# m365_esp32.net
KiCad netlist of a schematic drawn in EAGLE
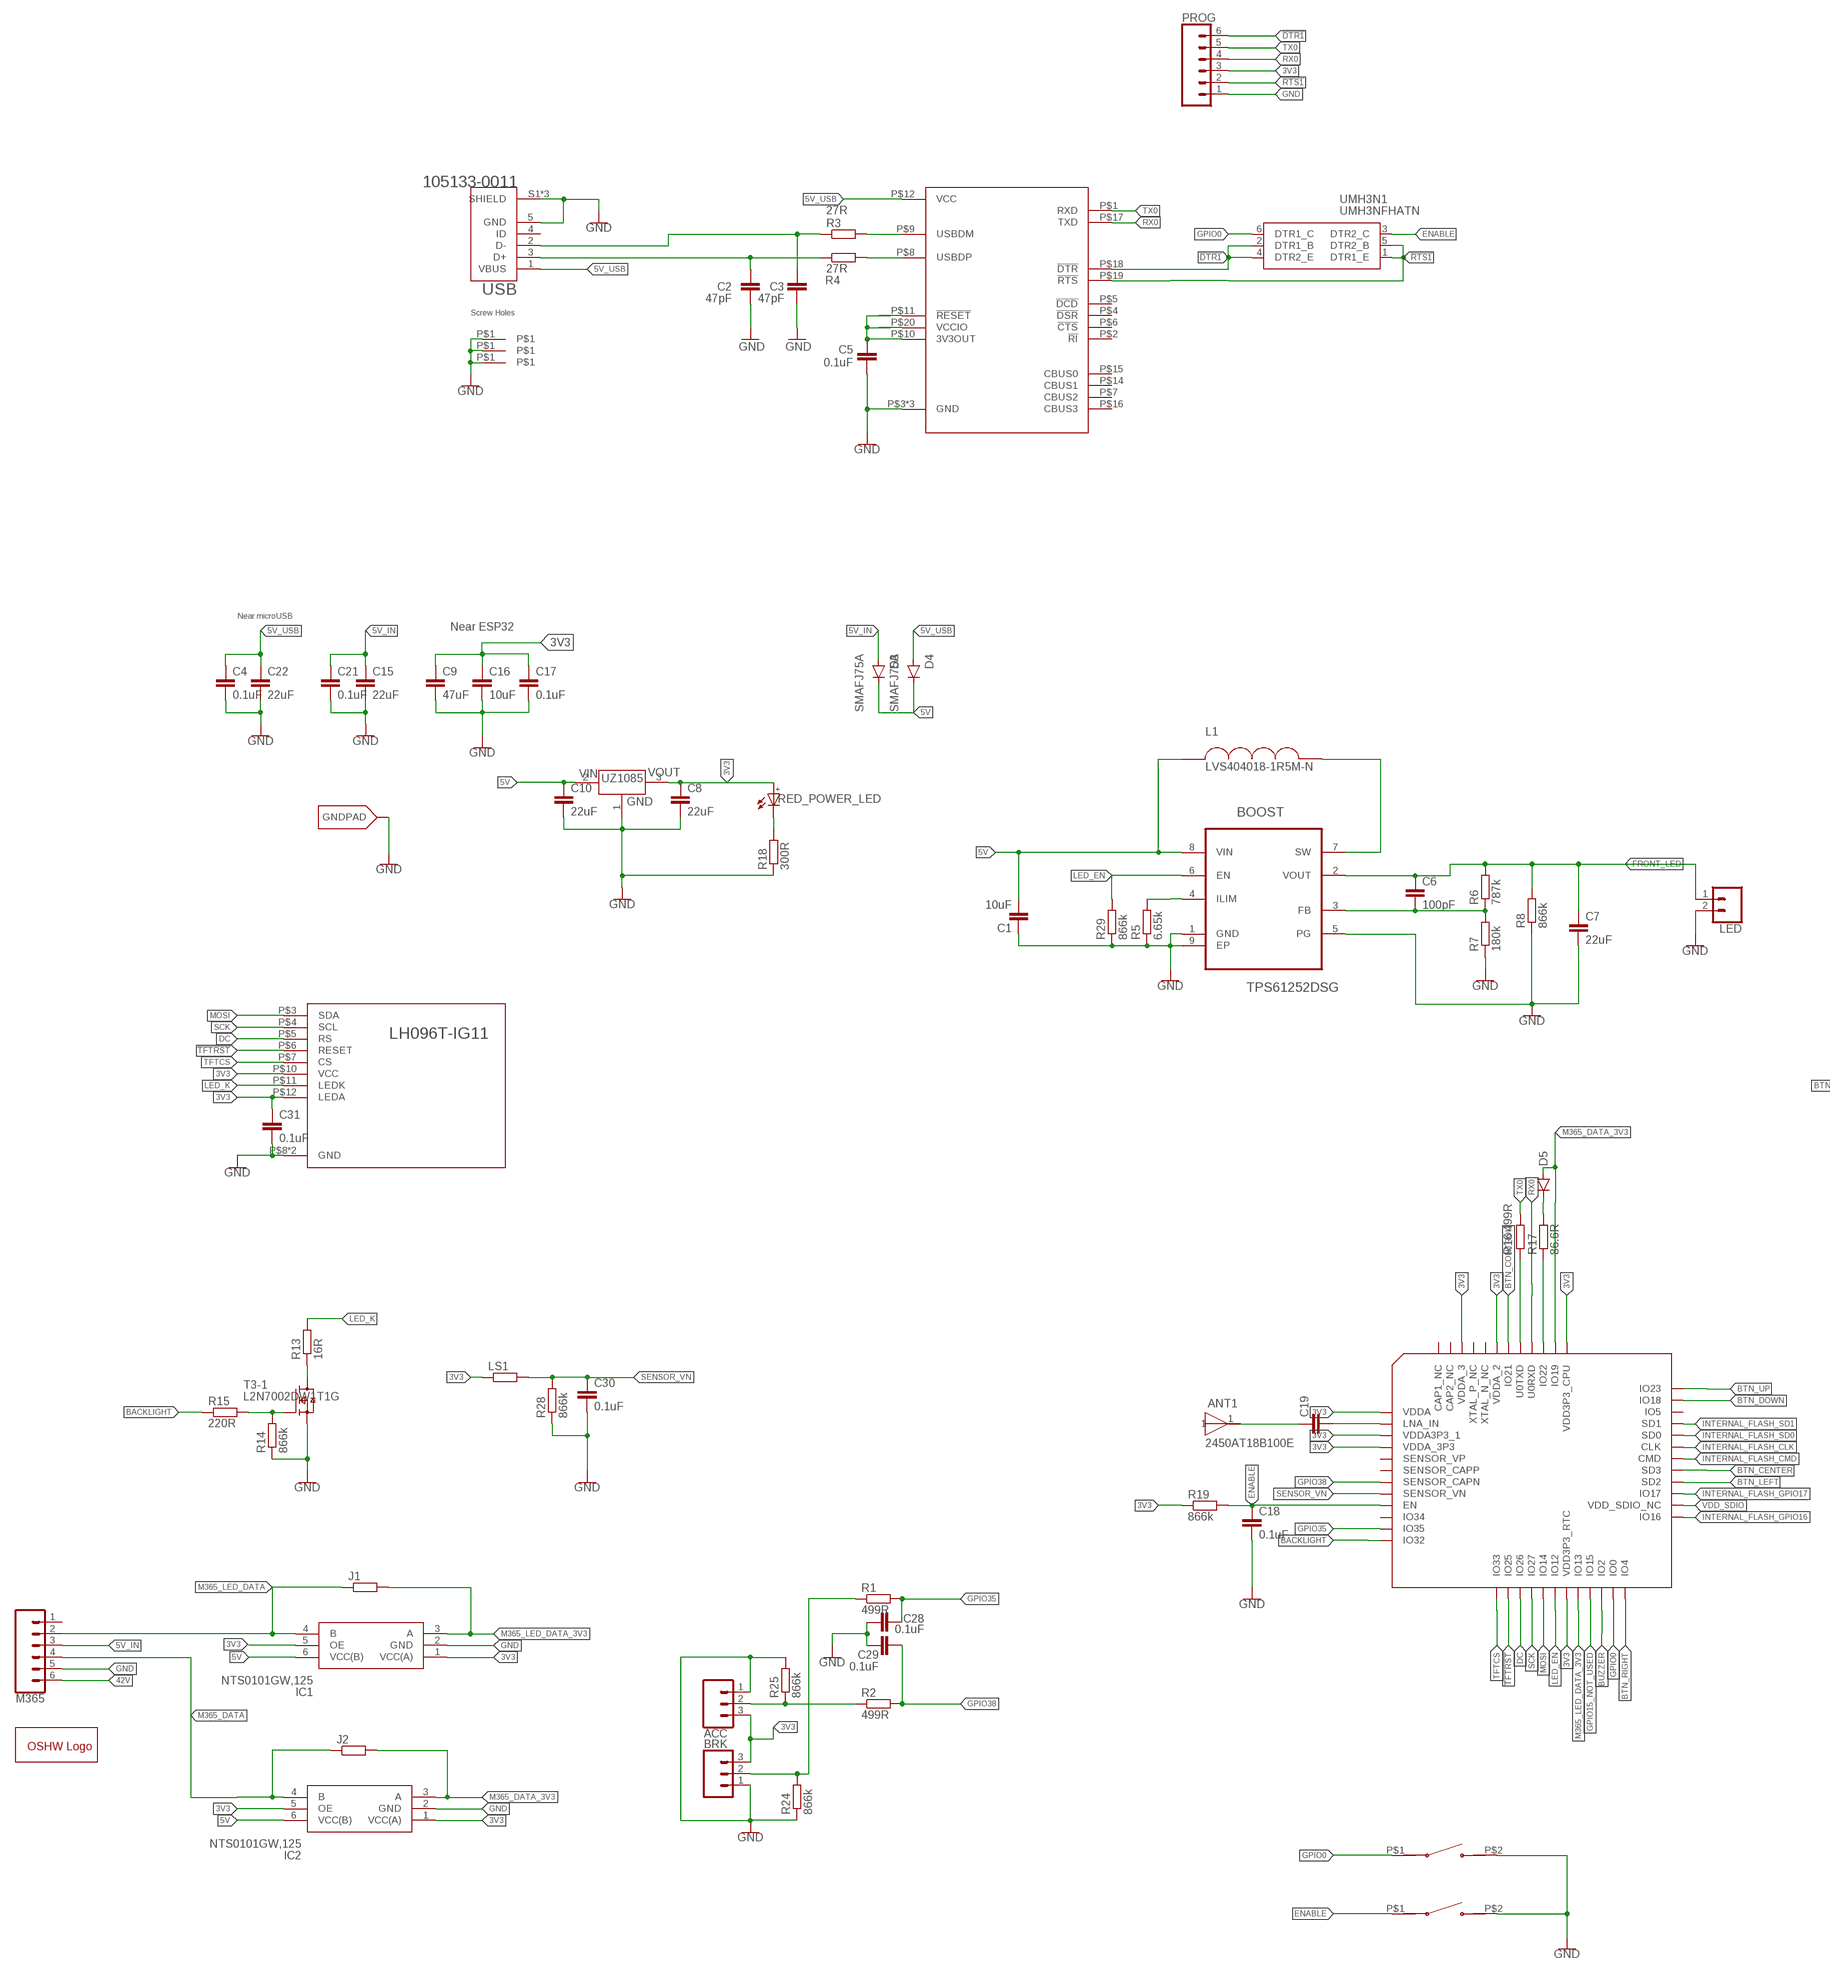
[diagram p0: schematic, sheet 1, part 1 of 2]
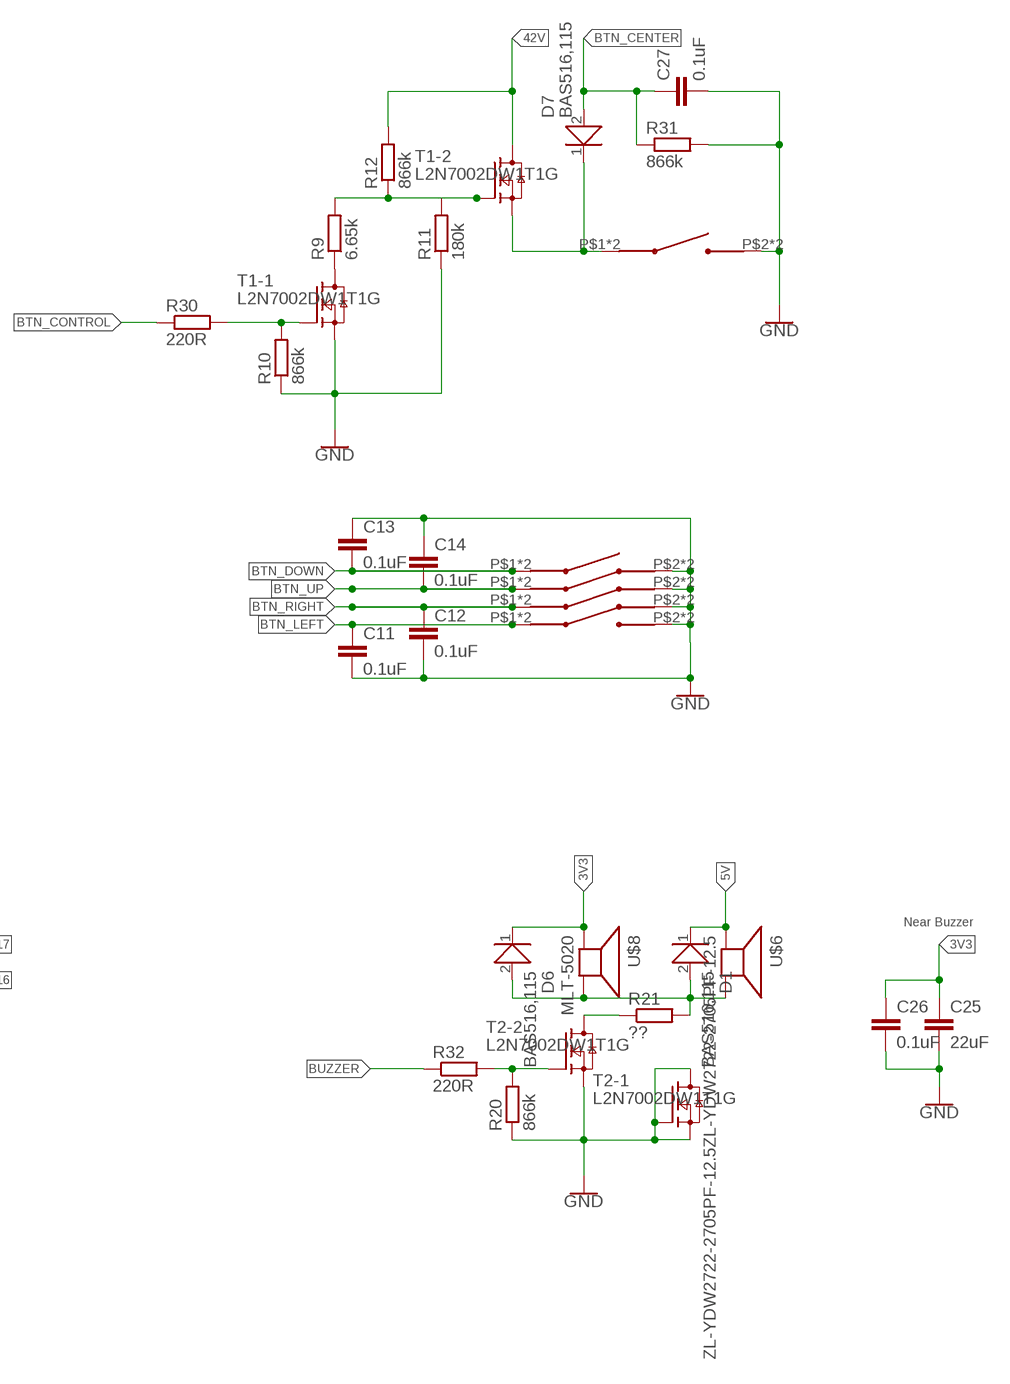
[diagram p1: schematic, sheet 1, part 2 of 2]

(export (version "E")
  (design (tool "Eeschema 10.0.6"))
  (components
    (comp (ref "ACC")
      (value "CONN_03LONGPADS")
      (footprint "eagle-import:1X03_LONGPADS")
      (libsource (lib "eagle-import") (part "CONN_03LONGPADS"))
    )
    (comp (ref "ANT1")
      (value "2450AT18B100E")
      (footprint "eagle-import:ANT_2450AT18B100E")
      (fields (field (name "MF") "Johanson Technology"))
      (libsource (lib "eagle-import") (part "2450AT18B100E"))
    )
    (comp (ref "BOOST")
      (value "TPS61252DSG")
      (footprint "eagle-import:SON50P200X200X80-9N")
      (fields (field (name "MF") "Texas Instruments"))
      (libsource (lib "eagle-import") (part "TPS61252DSG"))
    )
    (comp (ref "BRK")
      (value "CONN_03LONGPADS")
      (footprint "eagle-import:1X03_LONGPADS")
      (libsource (lib "eagle-import") (part "CONN_03LONGPADS"))
    )
    (comp (ref "C1")
      (value "10uF")
      (footprint "eagle-import:C1206")
      (libsource (lib "eagle-import") (part "CC1206"))
    )
    (comp (ref "C2")
      (value "47pF")
      (footprint "eagle-import:C0402")
      (libsource (lib "eagle-import") (part "C-EUC0402"))
    )
    (comp (ref "C3")
      (value "47pF")
      (footprint "eagle-import:C0402")
      (libsource (lib "eagle-import") (part "C-EUC0402"))
    )
    (comp (ref "C4")
      (value "0.1uF")
      (footprint "eagle-import:C0402")
      (libsource (lib "eagle-import") (part "CC0402"))
    )
    (comp (ref "C5")
      (value "0.1uF")
      (footprint "eagle-import:C0402")
      (libsource (lib "eagle-import") (part "CC0402"))
    )
    (comp (ref "C6")
      (value "100pF")
      (footprint "eagle-import:C0603")
      (libsource (lib "eagle-import") (part "CC0603"))
    )
    (comp (ref "C7")
      (value "22uF")
      (footprint "eagle-import:C0603")
      (libsource (lib "eagle-import") (part "CC0603"))
    )
    (comp (ref "C8")
      (value "22uF")
      (footprint "eagle-import:C0603")
      (libsource (lib "eagle-import") (part "CC0603"))
    )
    (comp (ref "C9")
      (value "47uF")
      (footprint "eagle-import:C0603")
      (libsource (lib "eagle-import") (part "CC0603"))
    )
    (comp (ref "C10")
      (value "22uF")
      (footprint "eagle-import:C0603")
      (libsource (lib "eagle-import") (part "CC0603"))
    )
    (comp (ref "C11")
      (value "0.1uF")
      (footprint "eagle-import:C0402")
      (libsource (lib "eagle-import") (part "CC0402"))
    )
    (comp (ref "C12")
      (value "0.1uF")
      (footprint "eagle-import:C0402")
      (libsource (lib "eagle-import") (part "CC0402"))
    )
    (comp (ref "C13")
      (value "0.1uF")
      (footprint "eagle-import:C0402")
      (libsource (lib "eagle-import") (part "CC0402"))
    )
    (comp (ref "C14")
      (value "0.1uF")
      (footprint "eagle-import:C0402")
      (libsource (lib "eagle-import") (part "CC0402"))
    )
    (comp (ref "C15")
      (value "22uF")
      (footprint "eagle-import:C0603")
      (libsource (lib "eagle-import") (part "CC0603"))
    )
    (comp (ref "C16")
      (value "10uF")
      (footprint "eagle-import:C0402")
      (libsource (lib "eagle-import") (part "CC0402"))
    )
    (comp (ref "C17")
      (value "0.1uF")
      (footprint "eagle-import:C0402")
      (libsource (lib "eagle-import") (part "CC0402"))
    )
    (comp (ref "C18")
      (value "0.1uF")
      (footprint "eagle-import:C0402")
      (libsource (lib "eagle-import") (part "CC0402"))
    )
    (comp (ref "C19")
      (value "CC0402")
      (footprint "eagle-import:C0402")
      (libsource (lib "eagle-import") (part "CC0402"))
    )
    (comp (ref "C21")
      (value "0.1uF")
      (footprint "eagle-import:C0402")
      (libsource (lib "eagle-import") (part "CC0402"))
    )
    (comp (ref "C22")
      (value "22uF")
      (footprint "eagle-import:C0603")
      (libsource (lib "eagle-import") (part "CC0603"))
    )
    (comp (ref "C25")
      (value "22uF")
      (footprint "eagle-import:C0603")
      (libsource (lib "eagle-import") (part "CC0603"))
    )
    (comp (ref "C26")
      (value "0.1uF")
      (footprint "eagle-import:C0402")
      (libsource (lib "eagle-import") (part "CC0402"))
    )
    (comp (ref "C27")
      (value "0.1uF")
      (footprint "eagle-import:C0402")
      (libsource (lib "eagle-import") (part "CC0402"))
    )
    (comp (ref "C28")
      (value "0.1uF")
      (footprint "eagle-import:C0402")
      (libsource (lib "eagle-import") (part "CC0402"))
    )
    (comp (ref "C29")
      (value "0.1uF")
      (footprint "eagle-import:C0402")
      (libsource (lib "eagle-import") (part "CC0402"))
    )
    (comp (ref "C30")
      (value "0.1uF")
      (footprint "eagle-import:C0402")
      (libsource (lib "eagle-import") (part "CC0402"))
    )
    (comp (ref "C31")
      (value "0.1uF")
      (footprint "eagle-import:C0402")
      (libsource (lib "eagle-import") (part "CC0402"))
    )
    (comp (ref "CENTER")
      (value "KSEK43J")
      (footprint "eagle-import:KSEK43J")
      (libsource (lib "eagle-import") (part "KSEK43J"))
    )
    (comp (ref "D1")
      (value "BAS516,115")
      (footprint "eagle-import:SOD1608X65N")
      (fields (field (name "MOUSER_PART_NUMBER") "771-BAS516-T/R") (field (name "RS_PART_NUMBER") "0508282"))
      (libsource (lib "eagle-import") (part "BAS516,115"))
    )
    (comp (ref "D3")
      (value "SMAFJ75A")
      (footprint "eagle-import:SMAFJ75A")
      (libsource (lib "eagle-import") (part "SMAFJ75A"))
    )
    (comp (ref "D4")
      (value "SMAFJ75A")
      (footprint "eagle-import:SMAFJ75A")
      (libsource (lib "eagle-import") (part "SMAFJ75A"))
    )
    (comp (ref "D5")
      (value "SMAFJ75A")
      (footprint "eagle-import:SMAFJ75A")
      (libsource (lib "eagle-import") (part "SMAFJ75A"))
    )
    (comp (ref "D6")
      (value "BAS516,115")
      (footprint "eagle-import:SOD1608X65N")
      (fields (field (name "MOUSER_PART_NUMBER") "771-BAS516-T/R") (field (name "RS_PART_NUMBER") "0508282"))
      (libsource (lib "eagle-import") (part "BAS516,115"))
    )
    (comp (ref "D7")
      (value "BAS516,115")
      (footprint "eagle-import:SOD1608X65N")
      (fields (field (name "MOUSER_PART_NUMBER") "771-BAS516-T/R") (field (name "RS_PART_NUMBER") "0508282"))
      (libsource (lib "eagle-import") (part "BAS516,115"))
    )
    (comp (ref "DOWN")
      (value "KSEK43J")
      (footprint "eagle-import:KSEK43J")
      (libsource (lib "eagle-import") (part "KSEK43J"))
    )
    (comp (ref "FT231X")
      (value "FT231XQ-R")
      (footprint "eagle-import:FT231XQ-R")
      (libsource (lib "eagle-import") (part "FT231XQ-R"))
    )
    (comp (ref "GOLD_ORB_SM2")
      (value "OSHWLOGOLOGO5MM")
      (footprint "eagle-import:OSHW_5MM")
      (libsource (lib "eagle-import") (part "OSHWLOGOLOGO5MM"))
    )
    (comp (ref "IC1")
      (value "NTS0101GW,125")
      (footprint "eagle-import:SOT65P210X110-6N")
      (fields (field (name "MOUSER_PART_NUMBER") "771-NTS0101GW125"))
      (libsource (lib "eagle-import") (part "NTS0101GW,125"))
    )
    (comp (ref "IC2")
      (value "NTS0101GW,125")
      (footprint "eagle-import:SOT65P210X110-6N")
      (fields (field (name "MOUSER_PART_NUMBER") "771-NTS0101GW125"))
      (libsource (lib "eagle-import") (part "NTS0101GW,125"))
    )
    (comp (ref "IC3")
      (value "UNEXPECTEDMAKER_ESP32-PICO-D4")
      (footprint "eagle-import:UNEXPECTEDMAKER_PICO-D4-QFN48")
      (libsource (lib "eagle-import") (part "UNEXPECTEDMAKER_ESP32-PICO-D4"))
    )
    (comp (ref "J1")
      (value "RR0402")
      (footprint "eagle-import:R0402")
      (libsource (lib "eagle-import") (part "RR0402"))
    )
    (comp (ref "J2")
      (value "RR0402")
      (footprint "eagle-import:R0402")
      (libsource (lib "eagle-import") (part "RR0402"))
    )
    (comp (ref "L1")
      (value "LVS404018-1R5M-N")
      (footprint "eagle-import:LVS404018")
      (libsource (lib "eagle-import") (part "LVS404018-1R5M-N"))
    )
    (comp (ref "LED")
      (value "CONN_02PTH3")
      (footprint "eagle-import:1X02_LONGPADS")
      (libsource (lib "eagle-import") (part "CONN_02PTH3"))
    )
    (comp (ref "LEFT")
      (value "KSEK43J")
      (footprint "eagle-import:KSEK43J")
      (libsource (lib "eagle-import") (part "KSEK43J"))
    )
    (comp (ref "LS1")
      (value "RR1206")
      (footprint "eagle-import:R1206")
      (libsource (lib "eagle-import") (part "RR1206"))
    )
    (comp (ref "M365")
      (value "CONN_06LONGPADS")
      (footprint "eagle-import:1X06_LONGPADS")
      (libsource (lib "eagle-import") (part "CONN_06LONGPADS"))
    )
    (comp (ref "PROG")
      (value "CONN_06LOCK")
      (footprint "eagle-import:1X06_LOCK")
      (libsource (lib "eagle-import") (part "CONN_06LOCK"))
    )
    (comp (ref "R1")
      (value "499R")
      (footprint "eagle-import:R0402")
      (libsource (lib "eagle-import") (part "RR0402"))
    )
    (comp (ref "R2")
      (value "499R")
      (footprint "eagle-import:R0402")
      (libsource (lib "eagle-import") (part "RR0402"))
    )
    (comp (ref "R3")
      (value "27R")
      (footprint "eagle-import:R0402")
      (libsource (lib "eagle-import") (part "R-EU_R0402"))
    )
    (comp (ref "R4")
      (value "27R")
      (footprint "eagle-import:R0402")
      (libsource (lib "eagle-import") (part "R-EU_R0402"))
    )
    (comp (ref "R5")
      (value "6.65k")
      (footprint "eagle-import:R0402")
      (libsource (lib "eagle-import") (part "RR0402"))
    )
    (comp (ref "R6")
      (value "787k")
      (footprint "eagle-import:R0603")
      (libsource (lib "eagle-import") (part "RR0603"))
    )
    (comp (ref "R7")
      (value "180k")
      (footprint "eagle-import:R0603")
      (libsource (lib "eagle-import") (part "RR0603"))
    )
    (comp (ref "R8")
      (value "866k")
      (footprint "eagle-import:R0402")
      (libsource (lib "eagle-import") (part "RR0402"))
    )
    (comp (ref "R9")
      (value "6.65k")
      (footprint "eagle-import:R0402")
      (libsource (lib "eagle-import") (part "RR0402"))
    )
    (comp (ref "R10")
      (value "866k")
      (footprint "eagle-import:R0402")
      (libsource (lib "eagle-import") (part "RR0402"))
    )
    (comp (ref "R11")
      (value "180k")
      (footprint "eagle-import:R0603")
      (libsource (lib "eagle-import") (part "RR0603"))
    )
    (comp (ref "R12")
      (value "866k")
      (footprint "eagle-import:R0402")
      (libsource (lib "eagle-import") (part "RR0402"))
    )
    (comp (ref "R13")
      (value "16R")
      (footprint "eagle-import:R0402")
      (libsource (lib "eagle-import") (part "RR0402"))
    )
    (comp (ref "R14")
      (value "866k")
      (footprint "eagle-import:R0402")
      (libsource (lib "eagle-import") (part "RR0402"))
    )
    (comp (ref "R15")
      (value "220R")
      (footprint "eagle-import:R0402")
      (libsource (lib "eagle-import") (part "RR0402"))
    )
    (comp (ref "R16")
      (value "499R")
      (footprint "eagle-import:R0402")
      (libsource (lib "eagle-import") (part "RR0402"))
    )
    (comp (ref "R17")
      (value "86.6R")
      (footprint "eagle-import:R0402")
      (libsource (lib "eagle-import") (part "RR0402"))
    )
    (comp (ref "R18")
      (value "300R")
      (footprint "eagle-import:R0402")
      (libsource (lib "eagle-import") (part "RR0402"))
    )
    (comp (ref "R19")
      (value "866k")
      (footprint "eagle-import:R0402")
      (libsource (lib "eagle-import") (part "RR0402"))
    )
    (comp (ref "R20")
      (value "866k")
      (footprint "eagle-import:R0402")
      (libsource (lib "eagle-import") (part "RR0402"))
    )
    (comp (ref "R21")
      (value "??")
      (footprint "eagle-import:R0805")
      (libsource (lib "eagle-import") (part "R"))
    )
    (comp (ref "R24")
      (value "866k")
      (footprint "eagle-import:R0402")
      (libsource (lib "eagle-import") (part "RR0402"))
    )
    (comp (ref "R25")
      (value "866k")
      (footprint "eagle-import:R0402")
      (libsource (lib "eagle-import") (part "RR0402"))
    )
    (comp (ref "R28")
      (value "866k")
      (footprint "eagle-import:R0402")
      (libsource (lib "eagle-import") (part "RR0402"))
    )
    (comp (ref "R29")
      (value "866k")
      (footprint "eagle-import:R0402")
      (libsource (lib "eagle-import") (part "RR0402"))
    )
    (comp (ref "R30")
      (value "220R")
      (footprint "eagle-import:R0402")
      (libsource (lib "eagle-import") (part "RR0402"))
    )
    (comp (ref "R31")
      (value "866k")
      (footprint "eagle-import:R0402")
      (libsource (lib "eagle-import") (part "RR0402"))
    )
    (comp (ref "R32")
      (value "220R")
      (footprint "eagle-import:R0402")
      (libsource (lib "eagle-import") (part "RR0402"))
    )
    (comp (ref "RED_POWER_LED")
      (value "WL-SMCD_0603_150060BS55040")
      (footprint "eagle-import:WL-SMCD_0603")
      (libsource (lib "eagle-import") (part "WL-SMCD_0603_150060BS55040"))
    )
    (comp (ref "REG")
      (value "UZ1085L-33-TN3-R")
      (footprint "eagle-import:TO-252-2")
      (libsource (lib "eagle-import") (part "UZ1085L-33-TN3-R"))
    )
    (comp (ref "RIGHT")
      (value "KSEK43J")
      (footprint "eagle-import:KSEK43J")
      (libsource (lib "eagle-import") (part "KSEK43J"))
    )
    (comp (ref "T1")
      (value "L2N7002DW1T1G")
      (footprint "eagle-import:SOT363")
      (libsource (lib "eagle-import") (part "2N7002PS"))
    )
    (comp (ref "T2")
      (value "L2N7002DW1T1G")
      (footprint "eagle-import:SOT363")
      (libsource (lib "eagle-import") (part "2N7002PS"))
    )
    (comp (ref "T3")
      (value "L2N7002DW1T1G")
      (footprint "eagle-import:SOT363")
      (libsource (lib "eagle-import") (part "2N7002PS"))
    )
    (comp (ref "U$1")
      (value "TL3302BF260QJ")
      (footprint "eagle-import:TL3302BF260QJ")
      (libsource (lib "eagle-import") (part "TL3302BF260QJ"))
    )
    (comp (ref "U$2")
      (value "TL3302BF260QJ")
      (footprint "eagle-import:TL3302BF260QJ")
      (libsource (lib "eagle-import") (part "TL3302BF260QJ"))
    )
    (comp (ref "U$3")
      (value "SCREWHOLE-M2")
      (footprint "eagle-import:SCREWHOLE-M2")
      (libsource (lib "eagle-import") (part "SCREWHOLE-M2"))
    )
    (comp (ref "U$4")
      (value "SCREWHOLE-M2")
      (footprint "eagle-import:SCREWHOLE-M2")
      (libsource (lib "eagle-import") (part "SCREWHOLE-M2"))
    )
    (comp (ref "U$5")
      (value "SCREWHOLE-M2")
      (footprint "eagle-import:SCREWHOLE-M2")
      (libsource (lib "eagle-import") (part "SCREWHOLE-M2"))
    )
    (comp (ref "U$6")
      (value "ZL-YDW2722-2705PF-12.5ZL-YDW2722-2705PF-12.5")
      (footprint "eagle-import:ZL-YDW2722-2705PF-12.5")
      (libsource (lib "eagle-import") (part "ZL-YDW2722-2705PF-12.5ZL-YDW2722-2705PF-12.5"))
    )
    (comp (ref "U$8")
      (value "MLT-5020")
      (footprint "eagle-import:MLT-5020")
      (libsource (lib "eagle-import") (part "MLT-5020"))
    )
    (comp (ref "U$11")
      (value "LH096T-IG11")
      (footprint "eagle-import:LH096T-IG11")
      (libsource (lib "eagle-import") (part "LH096T-IG11"))
    )
    (comp (ref "UMH3N1")
      (value "UMH3NFHATN")
      (footprint "eagle-import:SOT65P210X100-6N")
      (fields (field (name "MOUSER_PART_NUMBER") "755-UMH3NFHATN"))
      (libsource (lib "eagle-import") (part "UMH3NFHATN"))
    )
    (comp (ref "UP")
      (value "KSEK43J")
      (footprint "eagle-import:KSEK43J")
      (libsource (lib "eagle-import") (part "KSEK43J"))
    )
    (comp (ref "USB")
      (value "105133-0011")
      (footprint "eagle-import:MOLEX_105133-0011")
      (fields (field (name "MF") "Molex"))
      (libsource (lib "eagle-import") (part "105133-0011"))
    )
  )
  (nets
    (net (code "1") (name "/~{DTR1}") (class "Default")
      (node (ref "FT231X") (pin "P$18") (pinfunction "~{DTR}_P$18") (pintype "bidirectional"))
      (node (ref "PROG") (pin "6") (pinfunction "6_6") (pintype "passive"))
      (node (ref "UMH3N1") (pin "2") (pinfunction "DTR1_B_2") (pintype "bidirectional"))
      (node (ref "UMH3N1") (pin "4") (pinfunction "DTR2_E_4") (pintype "bidirectional"))
    )
    (net (code "2") (name "/~{RTS1}") (class "Default")
      (node (ref "FT231X") (pin "P$19") (pinfunction "~{RTS}_P$19") (pintype "bidirectional"))
      (node (ref "PROG") (pin "2") (pinfunction "2_2") (pintype "passive"))
      (node (ref "UMH3N1") (pin "1") (pinfunction "DTR1_E_1") (pintype "bidirectional"))
      (node (ref "UMH3N1") (pin "5") (pinfunction "DTR2_B_5") (pintype "bidirectional"))
    )
    (net (code "3") (name "/~{TFTRST}") (class "Default")
      (node (ref "IC3") (pin "14") (pinfunction "IO25_14") (pintype "bidirectional"))
      (node (ref "U$11") (pin "P$6") (pinfunction "RESET_P$6") (pintype "bidirectional"))
    )
    (net (code "4") (name "3V3") (class "Default")
      (node (ref "ACC") (pin "3") (pinfunction "3_3") (pintype "passive"))
      (node (ref "BRK") (pin "3") (pinfunction "3_3") (pintype "passive"))
      (node (ref "C16") (pin "1") (pinfunction "1_1") (pintype "passive"))
      (node (ref "C17") (pin "1") (pinfunction "1_1") (pintype "passive"))
      (node (ref "C25") (pin "1") (pinfunction "1_1") (pintype "passive"))
      (node (ref "C26") (pin "1") (pinfunction "1_1") (pintype "passive"))
      (node (ref "C31") (pin "1") (pinfunction "1_1") (pintype "passive"))
      (node (ref "C8") (pin "1") (pinfunction "1_1") (pintype "passive"))
      (node (ref "C9") (pin "1") (pinfunction "1_1") (pintype "passive"))
      (node (ref "D6") (pin "1") (pinfunction "1_1") (pintype "bidirectional"))
      (node (ref "IC1") (pin "1") (pinfunction "VCC(A)_1") (pintype "bidirectional"))
      (node (ref "IC1") (pin "5") (pinfunction "OE_5") (pintype "bidirectional"))
      (node (ref "IC2") (pin "1") (pinfunction "VCC(A)_1") (pintype "bidirectional"))
      (node (ref "IC2") (pin "5") (pinfunction "OE_5") (pintype "bidirectional"))
      (node (ref "IC3") (pin "1") (pinfunction "VDDA_1") (pintype "bidirectional"))
      (node (ref "IC3") (pin "19") (pinfunction "VDD3P3_RTC_19") (pintype "bidirectional"))
      (node (ref "IC3") (pin "3") (pinfunction "VDDA3P3_1_3") (pintype "bidirectional"))
      (node (ref "IC3") (pin "37") (pinfunction "VDD3P3_CPU_37") (pintype "bidirectional"))
      (node (ref "IC3") (pin "4") (pinfunction "VDDA_3P3_4") (pintype "bidirectional"))
      (node (ref "IC3") (pin "43") (pinfunction "VDDA_2_43") (pintype "bidirectional"))
      (node (ref "IC3") (pin "46") (pinfunction "VDDA_3_46") (pintype "bidirectional"))
      (node (ref "LS1") (pin "1") (pinfunction "1_1") (pintype "passive"))
      (node (ref "PROG") (pin "3") (pinfunction "3_3") (pintype "passive"))
      (node (ref "R19") (pin "1") (pinfunction "1_1") (pintype "passive"))
      (node (ref "RED_POWER_LED") (pin "2") (pinfunction "A_2") (pintype "passive"))
      (node (ref "REG") (pin "3") (pinfunction "VOUT_3") (pintype "bidirectional"))
      (node (ref "U$11") (pin "P$10") (pinfunction "VCC_P$10") (pintype "bidirectional"))
      (node (ref "U$11") (pin "P$12") (pinfunction "LEDA_P$12") (pintype "bidirectional"))
      (node (ref "U$8") (pin "P$2") (pinfunction "+_P$2") (pintype "passive"))
    )
    (net (code "5") (name "5V") (class "Default")
      (node (ref "BOOST") (pin "8") (pinfunction "VIN_8") (pintype "power_in"))
      (node (ref "C1") (pin "2") (pinfunction "2_2") (pintype "passive"))
      (node (ref "C10") (pin "1") (pinfunction "1_1") (pintype "passive"))
      (node (ref "D1") (pin "1") (pinfunction "1_1") (pintype "bidirectional"))
      (node (ref "D3") (pin "P$1") (pinfunction "CATHODE_P$1") (pintype "bidirectional"))
      (node (ref "D4") (pin "P$1") (pinfunction "CATHODE_P$1") (pintype "bidirectional"))
      (node (ref "IC1") (pin "6") (pinfunction "VCC(B)_6") (pintype "bidirectional"))
      (node (ref "IC2") (pin "6") (pinfunction "VCC(B)_6") (pintype "bidirectional"))
      (node (ref "L1") (pin "P$1") (pinfunction "P$1_P$1") (pintype "bidirectional"))
      (node (ref "REG") (pin "2") (pinfunction "VIN_2") (pintype "bidirectional"))
      (node (ref "U$6") (pin "P$1") (pinfunction "+_P$1") (pintype "passive"))
    )
    (net (code "6") (name "5V_IN") (class "Default")
      (node (ref "C15") (pin "1") (pinfunction "1_1") (pintype "passive"))
      (node (ref "C21") (pin "1") (pinfunction "1_1") (pintype "passive"))
      (node (ref "D3") (pin "P$2") (pinfunction "ANODE_P$2") (pintype "bidirectional"))
      (node (ref "M365") (pin "3") (pinfunction "3_3") (pintype "passive"))
    )
    (net (code "7") (name "5V_USB") (class "Default")
      (node (ref "C22") (pin "1") (pinfunction "1_1") (pintype "passive"))
      (node (ref "C4") (pin "1") (pinfunction "1_1") (pintype "passive"))
      (node (ref "D4") (pin "P$2") (pinfunction "ANODE_P$2") (pintype "bidirectional"))
      (node (ref "FT231X") (pin "P$12") (pinfunction "VCC_P$12") (pintype "bidirectional"))
      (node (ref "USB") (pin "1") (pinfunction "VBUS_1") (pintype "passive"))
    )
    (net (code "8") (name "42V") (class "Default")
      (node (ref "M365") (pin "6") (pinfunction "6_6") (pintype "passive"))
      (node (ref "R12") (pin "2") (pinfunction "2_2") (pintype "passive"))
      (node (ref "T1") (pin "3") (pinfunction "D_3") (pintype "passive"))
    )
    (net (code "9") (name "BACKLIGHT") (class "Default")
      (node (ref "IC3") (pin "12") (pinfunction "IO32_12") (pintype "bidirectional"))
      (node (ref "R15") (pin "1") (pinfunction "1_1") (pintype "passive"))
    )
    (net (code "10") (name "BTN_CENTER") (class "Default")
      (node (ref "C27") (pin "1") (pinfunction "1_1") (pintype "passive"))
      (node (ref "D7") (pin "2") (pinfunction "2_2") (pintype "bidirectional"))
      (node (ref "IC3") (pin "29") (pinfunction "SD3_29") (pintype "bidirectional"))
      (node (ref "R31") (pin "1") (pinfunction "1_1") (pintype "passive"))
    )
    (net (code "11") (name "BTN_CONTROL") (class "Default")
      (node (ref "IC3") (pin "42") (pinfunction "IO21_42") (pintype "power_in"))
      (node (ref "R30") (pin "1") (pinfunction "1_1") (pintype "passive"))
    )
    (net (code "12") (name "BTN_DOWN") (class "Default")
      (node (ref "C13") (pin "2") (pinfunction "2_2") (pintype "passive"))
      (node (ref "DOWN") (pin "P$1") (pinfunction "P$1_P$1") (pintype "bidirectional"))
      (node (ref "DOWN") (pin "P$4") (pinfunction "P$1_P$4") (pintype "bidirectional"))
      (node (ref "IC3") (pin "35") (pinfunction "IO18_35") (pintype "bidirectional"))
    )
    (net (code "13") (name "BTN_LEFT") (class "Default")
      (node (ref "C11") (pin "1") (pinfunction "1_1") (pintype "passive"))
      (node (ref "IC3") (pin "28") (pinfunction "SD2_28") (pintype "bidirectional"))
      (node (ref "LEFT") (pin "P$1") (pinfunction "P$1_P$1") (pintype "bidirectional"))
      (node (ref "LEFT") (pin "P$4") (pinfunction "P$1_P$4") (pintype "bidirectional"))
    )
    (net (code "14") (name "BTN_RIGHT") (class "Default")
      (node (ref "C12") (pin "1") (pinfunction "1_1") (pintype "passive"))
      (node (ref "IC3") (pin "24") (pinfunction "IO4_24") (pintype "bidirectional"))
      (node (ref "RIGHT") (pin "P$1") (pinfunction "P$1_P$1") (pintype "bidirectional"))
      (node (ref "RIGHT") (pin "P$4") (pinfunction "P$1_P$4") (pintype "bidirectional"))
    )
    (net (code "15") (name "BTN_UP") (class "Default")
      (node (ref "C14") (pin "2") (pinfunction "2_2") (pintype "passive"))
      (node (ref "IC3") (pin "36") (pinfunction "IO23_36") (pintype "bidirectional"))
      (node (ref "UP") (pin "P$1") (pinfunction "P$1_P$1") (pintype "bidirectional"))
      (node (ref "UP") (pin "P$4") (pinfunction "P$1_P$4") (pintype "bidirectional"))
    )
    (net (code "16") (name "BUZZER") (class "Default")
      (node (ref "IC3") (pin "22") (pinfunction "IO2_22") (pintype "bidirectional"))
      (node (ref "R32") (pin "1") (pinfunction "1_1") (pintype "passive"))
    )
    (net (code "17") (name "DC") (class "Default")
      (node (ref "IC3") (pin "15") (pinfunction "IO26_15") (pintype "bidirectional"))
      (node (ref "U$11") (pin "P$5") (pinfunction "RS_P$5") (pintype "bidirectional"))
    )
    (net (code "18") (name "ENABLE") (class "Default")
      (node (ref "C18") (pin "1") (pinfunction "1_1") (pintype "passive"))
      (node (ref "IC3") (pin "9") (pinfunction "EN_9") (pintype "bidirectional"))
      (node (ref "R19") (pin "2") (pinfunction "2_2") (pintype "passive"))
      (node (ref "U$2") (pin "P$1") (pinfunction "P$1_P$1") (pintype "bidirectional"))
      (node (ref "UMH3N1") (pin "3") (pinfunction "DTR2_C_3") (pintype "bidirectional"))
    )
    (net (code "19") (name "FRONT_LED") (class "Default")
      (node (ref "BOOST") (pin "2") (pinfunction "VOUT_2") (pintype "output"))
      (node (ref "C6") (pin "1") (pinfunction "1_1") (pintype "passive"))
      (node (ref "C7") (pin "1") (pinfunction "1_1") (pintype "passive"))
      (node (ref "LED") (pin "1") (pinfunction "1_1") (pintype "passive"))
      (node (ref "R6") (pin "2") (pinfunction "2_2") (pintype "passive"))
      (node (ref "R8") (pin "2") (pinfunction "2_2") (pintype "passive"))
    )
    (net (code "20") (name "GND") (class "Default")
      (node (ref "ACC") (pin "1") (pinfunction "1_1") (pintype "passive"))
      (node (ref "BOOST") (pin "1") (pinfunction "GND_1") (pintype "passive"))
      (node (ref "BOOST") (pin "5") (pinfunction "PG_5") (pintype "output"))
      (node (ref "BOOST") (pin "9") (pinfunction "EP_9") (pintype "passive"))
      (node (ref "BRK") (pin "1") (pinfunction "1_1") (pintype "passive"))
      (node (ref "C1") (pin "1") (pinfunction "1_1") (pintype "passive"))
      (node (ref "C10") (pin "2") (pinfunction "2_2") (pintype "passive"))
      (node (ref "C11") (pin "2") (pinfunction "2_2") (pintype "passive"))
      (node (ref "C12") (pin "2") (pinfunction "2_2") (pintype "passive"))
      (node (ref "C13") (pin "1") (pinfunction "1_1") (pintype "passive"))
      (node (ref "C14") (pin "1") (pinfunction "1_1") (pintype "passive"))
      (node (ref "C15") (pin "2") (pinfunction "2_2") (pintype "passive"))
      (node (ref "C16") (pin "2") (pinfunction "2_2") (pintype "passive"))
      (node (ref "C17") (pin "2") (pinfunction "2_2") (pintype "passive"))
      (node (ref "C18") (pin "2") (pinfunction "2_2") (pintype "passive"))
      (node (ref "C2") (pin "1") (pinfunction "1_1") (pintype "passive"))
      (node (ref "C21") (pin "2") (pinfunction "2_2") (pintype "passive"))
      (node (ref "C22") (pin "2") (pinfunction "2_2") (pintype "passive"))
      (node (ref "C25") (pin "2") (pinfunction "2_2") (pintype "passive"))
      (node (ref "C26") (pin "2") (pinfunction "2_2") (pintype "passive"))
      (node (ref "C27") (pin "2") (pinfunction "2_2") (pintype "passive"))
      (node (ref "C28") (pin "1") (pinfunction "1_1") (pintype "passive"))
      (node (ref "C29") (pin "1") (pinfunction "1_1") (pintype "passive"))
      (node (ref "C3") (pin "1") (pinfunction "1_1") (pintype "passive"))
      (node (ref "C30") (pin "2") (pinfunction "2_2") (pintype "passive"))
      (node (ref "C31") (pin "2") (pinfunction "2_2") (pintype "passive"))
      (node (ref "C4") (pin "2") (pinfunction "2_2") (pintype "passive"))
      (node (ref "C5") (pin "2") (pinfunction "2_2") (pintype "passive"))
      (node (ref "C7") (pin "2") (pinfunction "2_2") (pintype "passive"))
      (node (ref "C8") (pin "2") (pinfunction "2_2") (pintype "passive"))
      (node (ref "C9") (pin "2") (pinfunction "2_2") (pintype "passive"))
      (node (ref "CENTER") (pin "P$2") (pinfunction "P$2_P$2") (pintype "bidirectional"))
      (node (ref "CENTER") (pin "P$3") (pinfunction "P$2_P$3") (pintype "bidirectional"))
      (node (ref "DOWN") (pin "P$2") (pinfunction "P$2_P$2") (pintype "bidirectional"))
      (node (ref "DOWN") (pin "P$3") (pinfunction "P$2_P$3") (pintype "bidirectional"))
      (node (ref "FT231X") (pin "P$13") (pinfunction "GND_P$13") (pintype "bidirectional"))
      (node (ref "FT231X") (pin "P$21") (pinfunction "GND_P$21") (pintype "bidirectional"))
      (node (ref "FT231X") (pin "P$3") (pinfunction "GND_P$3") (pintype "bidirectional"))
      (node (ref "IC1") (pin "2") (pinfunction "GND_2") (pintype "bidirectional"))
      (node (ref "IC2") (pin "2") (pinfunction "GND_2") (pintype "bidirectional"))
      (node (ref "IC3") (pin "EXP") (pinfunction "GNDPAD_EXP") (pintype "power_in"))
      (node (ref "LED") (pin "2") (pinfunction "2_2") (pintype "passive"))
      (node (ref "LEFT") (pin "P$2") (pinfunction "P$2_P$2") (pintype "bidirectional"))
      (node (ref "LEFT") (pin "P$3") (pinfunction "P$2_P$3") (pintype "bidirectional"))
      (node (ref "M365") (pin "5") (pinfunction "5_5") (pintype "passive"))
      (node (ref "PROG") (pin "1") (pinfunction "1_1") (pintype "passive"))
      (node (ref "R10") (pin "1") (pinfunction "1_1") (pintype "passive"))
      (node (ref "R11") (pin "1") (pinfunction "1_1") (pintype "passive"))
      (node (ref "R14") (pin "1") (pinfunction "1_1") (pintype "passive"))
      (node (ref "R18") (pin "1") (pinfunction "1_1") (pintype "passive"))
      (node (ref "R20") (pin "1") (pinfunction "1_1") (pintype "passive"))
      (node (ref "R24") (pin "1") (pinfunction "1_1") (pintype "passive"))
      (node (ref "R25") (pin "2") (pinfunction "2_2") (pintype "passive"))
      (node (ref "R28") (pin "1") (pinfunction "1_1") (pintype "passive"))
      (node (ref "R29") (pin "1") (pinfunction "1_1") (pintype "passive"))
      (node (ref "R31") (pin "2") (pinfunction "2_2") (pintype "passive"))
      (node (ref "R5") (pin "1") (pinfunction "1_1") (pintype "passive"))
      (node (ref "R7") (pin "1") (pinfunction "1_1") (pintype "passive"))
      (node (ref "R8") (pin "1") (pinfunction "1_1") (pintype "passive"))
      (node (ref "REG") (pin "1") (pinfunction "GND_1") (pintype "bidirectional"))
      (node (ref "RIGHT") (pin "P$2") (pinfunction "P$2_P$2") (pintype "bidirectional"))
      (node (ref "RIGHT") (pin "P$3") (pinfunction "P$2_P$3") (pintype "bidirectional"))
      (node (ref "T1") (pin "1") (pinfunction "S_1") (pintype "passive"))
      (node (ref "T2") (pin "1") (pinfunction "S_1") (pintype "passive"))
      (node (ref "T2") (pin "2") (pinfunction "G_2") (pintype "passive"))
      (node (ref "T2") (pin "4") (pinfunction "S_4") (pintype "passive"))
      (node (ref "T2") (pin "6") (pinfunction "D_6") (pintype "passive"))
      (node (ref "T3") (pin "1") (pinfunction "S_1") (pintype "passive"))
      (node (ref "U$1") (pin "P$2") (pinfunction "P$2_P$2") (pintype "bidirectional"))
      (node (ref "U$11") (pin "P$13") (pinfunction "GND_P$13") (pintype "bidirectional"))
      (node (ref "U$11") (pin "P$8") (pinfunction "GND_P$8") (pintype "bidirectional"))
      (node (ref "U$2") (pin "P$2") (pinfunction "P$2_P$2") (pintype "bidirectional"))
      (node (ref "U$3") (pin "P$1") (pinfunction "P$1_P$1") (pintype "bidirectional"))
      (node (ref "U$4") (pin "P$1") (pinfunction "P$1_P$1") (pintype "bidirectional"))
      (node (ref "U$5") (pin "P$1") (pinfunction "P$1_P$1") (pintype "bidirectional"))
      (node (ref "UP") (pin "P$2") (pinfunction "P$2_P$2") (pintype "bidirectional"))
      (node (ref "UP") (pin "P$3") (pinfunction "P$2_P$3") (pintype "bidirectional"))
      (node (ref "USB") (pin "5") (pinfunction "GND_5") (pintype "passive"))
      (node (ref "USB") (pin "S1") (pinfunction "SHIELD_S1") (pintype "passive"))
      (node (ref "USB") (pin "S2") (pinfunction "SHIELD_S2") (pintype "passive"))
      (node (ref "USB") (pin "S3") (pinfunction "SHIELD_S3") (pintype "passive"))
    )
    (net (code "21") (name "GPIO0") (class "Default")
      (node (ref "IC3") (pin "23") (pinfunction "IO0_23") (pintype "bidirectional"))
      (node (ref "U$1") (pin "P$1") (pinfunction "P$1_P$1") (pintype "bidirectional"))
      (node (ref "UMH3N1") (pin "6") (pinfunction "DTR1_C_6") (pintype "bidirectional"))
    )
    (net (code "22") (name "GPIO15_NOT_USED") (class "Default")
      (node (ref "IC3") (pin "21") (pinfunction "IO15_21") (pintype "bidirectional"))
    )
    (net (code "23") (name "GPIO35") (class "Default")
      (node (ref "C28") (pin "2") (pinfunction "2_2") (pintype "passive"))
      (node (ref "IC3") (pin "11") (pinfunction "IO35_11") (pintype "bidirectional"))
      (node (ref "R1") (pin "2") (pinfunction "2_2") (pintype "passive"))
    )
    (net (code "24") (name "GPIO38") (class "Default")
      (node (ref "C29") (pin "2") (pinfunction "2_2") (pintype "passive"))
      (node (ref "IC3") (pin "7") (pinfunction "SENSOR_CAPN_7") (pintype "power_in"))
      (node (ref "R2") (pin "2") (pinfunction "2_2") (pintype "passive"))
    )
    (net (code "25") (name "INTERNAL_FLASH_CLK") (class "Default")
      (node (ref "IC3") (pin "31") (pinfunction "CLK_31") (pintype "bidirectional"))
    )
    (net (code "26") (name "INTERNAL_FLASH_CMD") (class "Default")
      (node (ref "IC3") (pin "30") (pinfunction "CMD_30") (pintype "bidirectional"))
    )
    (net (code "27") (name "INTERNAL_FLASH_GPIO16") (class "Default")
      (node (ref "IC3") (pin "25") (pinfunction "IO16_25") (pintype "bidirectional"))
    )
    (net (code "28") (name "INTERNAL_FLASH_GPIO17") (class "Default")
      (node (ref "IC3") (pin "27") (pinfunction "IO17_27") (pintype "bidirectional"))
    )
    (net (code "29") (name "INTERNAL_FLASH_SD0") (class "Default")
      (node (ref "IC3") (pin "32") (pinfunction "SD0_32") (pintype "bidirectional"))
    )
    (net (code "30") (name "INTERNAL_FLASH_SD1") (class "Default")
      (node (ref "IC3") (pin "33") (pinfunction "SD1_33") (pintype "bidirectional"))
    )
    (net (code "31") (name "LED_EN") (class "Default")
      (node (ref "BOOST") (pin "6") (pinfunction "EN_6") (pintype "input"))
      (node (ref "IC3") (pin "18") (pinfunction "IO12_18") (pintype "power_in"))
      (node (ref "R29") (pin "2") (pinfunction "2_2") (pintype "passive"))
    )
    (net (code "32") (name "LED_K") (class "Default")
      (node (ref "R13") (pin "2") (pinfunction "2_2") (pintype "passive"))
      (node (ref "U$11") (pin "P$11") (pinfunction "LEDK_P$11") (pintype "bidirectional"))
    )
    (net (code "33") (name "M365_DATA") (class "Default")
      (node (ref "IC2") (pin "4") (pinfunction "B_4") (pintype "bidirectional"))
      (node (ref "J2") (pin "1") (pinfunction "1_1") (pintype "passive"))
      (node (ref "M365") (pin "4") (pinfunction "4_4") (pintype "passive"))
    )
    (net (code "34") (name "M365_DATA_3V3") (class "Default")
      (node (ref "D5") (pin "P$2") (pinfunction "ANODE_P$2") (pintype "bidirectional"))
      (node (ref "IC2") (pin "3") (pinfunction "A_3") (pintype "bidirectional"))
      (node (ref "IC3") (pin "38") (pinfunction "IO19_38") (pintype "bidirectional"))
      (node (ref "J2") (pin "2") (pinfunction "2_2") (pintype "passive"))
    )
    (net (code "35") (name "M365_LED_DATA") (class "Default")
      (node (ref "IC1") (pin "4") (pinfunction "B_4") (pintype "bidirectional"))
      (node (ref "J1") (pin "1") (pinfunction "1_1") (pintype "passive"))
      (node (ref "M365") (pin "2") (pinfunction "2_2") (pintype "passive"))
    )
    (net (code "36") (name "M365_LED_DATA_3V3") (class "Default")
      (node (ref "IC1") (pin "3") (pinfunction "A_3") (pintype "bidirectional"))
      (node (ref "IC3") (pin "20") (pinfunction "IO13_20") (pintype "bidirectional"))
      (node (ref "J1") (pin "2") (pinfunction "2_2") (pintype "passive"))
    )
    (net (code "37") (name "MOSI") (class "Default")
      (node (ref "IC3") (pin "17") (pinfunction "IO14_17") (pintype "bidirectional"))
      (node (ref "U$11") (pin "P$3") (pinfunction "SDA_P$3") (pintype "bidirectional"))
    )
    (net (code "38") (name "Net-(ACC-Pad2)") (class "Default")
      (node (ref "ACC") (pin "2") (pinfunction "2_2") (pintype "passive"))
      (node (ref "R2") (pin "1") (pinfunction "1_1") (pintype "passive"))
      (node (ref "R25") (pin "1") (pinfunction "1_1") (pintype "passive"))
    )
    (net (code "39") (name "Net-(ANT1-Pad1)") (class "Default")
      (node (ref "ANT1") (pin "1") (pinfunction "1_1") (pintype "input"))
      (node (ref "C19") (pin "1") (pinfunction "1_1") (pintype "passive"))
    )
    (net (code "40") (name "Net-(BOOST-FB)") (class "Default")
      (node (ref "BOOST") (pin "3") (pinfunction "FB_3") (pintype "input"))
      (node (ref "C6") (pin "2") (pinfunction "2_2") (pintype "passive"))
      (node (ref "R6") (pin "1") (pinfunction "1_1") (pintype "passive"))
      (node (ref "R7") (pin "2") (pinfunction "2_2") (pintype "passive"))
    )
    (net (code "41") (name "Net-(BOOST-ILIM)") (class "Default")
      (node (ref "BOOST") (pin "4") (pinfunction "ILIM_4") (pintype "input"))
      (node (ref "R5") (pin "2") (pinfunction "2_2") (pintype "passive"))
    )
    (net (code "42") (name "Net-(BOOST-SW)") (class "Default")
      (node (ref "BOOST") (pin "7") (pinfunction "SW_7") (pintype "input"))
      (node (ref "L1") (pin "P$2") (pinfunction "P$2_P$2") (pintype "bidirectional"))
    )
    (net (code "43") (name "Net-(BRK-Pad2)") (class "Default")
      (node (ref "BRK") (pin "2") (pinfunction "2_2") (pintype "passive"))
      (node (ref "R1") (pin "1") (pinfunction "1_1") (pintype "passive"))
      (node (ref "R24") (pin "2") (pinfunction "2_2") (pintype "passive"))
    )
    (net (code "44") (name "Net-(D5-CATHODE)") (class "Default")
      (node (ref "D5") (pin "P$1") (pinfunction "CATHODE_P$1") (pintype "bidirectional"))
      (node (ref "R17") (pin "2") (pinfunction "2_2") (pintype "passive"))
    )
    (net (code "45") (name "Net-(FT231X-3V3OUT)") (class "Default")
      (node (ref "C5") (pin "1") (pinfunction "1_1") (pintype "passive"))
      (node (ref "FT231X") (pin "P$10") (pinfunction "3V3OUT_P$10") (pintype "bidirectional"))
      (node (ref "FT231X") (pin "P$11") (pinfunction "~{RESET}_P$11") (pintype "bidirectional"))
      (node (ref "FT231X") (pin "P$20") (pinfunction "VCCIO_P$20") (pintype "bidirectional"))
    )
    (net (code "46") (name "Net-(FT231X-USBDM)") (class "Default")
      (node (ref "FT231X") (pin "P$9") (pinfunction "USBDM_P$9") (pintype "bidirectional"))
      (node (ref "R3") (pin "2") (pinfunction "2_2") (pintype "passive"))
    )
    (net (code "47") (name "Net-(FT231X-USBDP)") (class "Default")
      (node (ref "FT231X") (pin "P$8") (pinfunction "USBDP_P$8") (pintype "bidirectional"))
      (node (ref "R4") (pin "2") (pinfunction "2_2") (pintype "passive"))
    )
    (net (code "48") (name "Net-(IC3A-IO22)") (class "Default")
      (node (ref "IC3") (pin "39") (pinfunction "IO22_39") (pintype "bidirectional"))
      (node (ref "R17") (pin "1") (pinfunction "1_1") (pintype "passive"))
    )
    (net (code "49") (name "Net-(IC3A-LNA_IN)") (class "Default")
      (node (ref "C19") (pin "2") (pinfunction "2_2") (pintype "passive"))
      (node (ref "IC3") (pin "2") (pinfunction "LNA_IN_2") (pintype "bidirectional"))
    )
    (net (code "50") (name "Net-(IC3A-U0TXD)") (class "Default")
      (node (ref "IC3") (pin "41") (pinfunction "U0TXD_41") (pintype "bidirectional"))
      (node (ref "R16") (pin "1") (pinfunction "1_1") (pintype "passive"))
    )
    (net (code "51") (name "Net-(RED_POWER_LED-C)") (class "Default")
      (node (ref "R18") (pin "2") (pinfunction "2_2") (pintype "passive"))
      (node (ref "RED_POWER_LED") (pin "1") (pinfunction "C_1") (pintype "passive"))
    )
    (net (code "52") (name "Net-(T1A-D)") (class "Default")
      (node (ref "R9") (pin "1") (pinfunction "1_1") (pintype "passive"))
      (node (ref "T1") (pin "6") (pinfunction "D_6") (pintype "passive"))
    )
    (net (code "53") (name "Net-(T1A-G)") (class "Default")
      (node (ref "R10") (pin "2") (pinfunction "2_2") (pintype "passive"))
      (node (ref "R30") (pin "2") (pinfunction "2_2") (pintype "passive"))
      (node (ref "T1") (pin "2") (pinfunction "G_2") (pintype "passive"))
    )
    (net (code "54") (name "Net-(T1B-G)") (class "Default")
      (node (ref "R11") (pin "2") (pinfunction "2_2") (pintype "passive"))
      (node (ref "R12") (pin "1") (pinfunction "1_1") (pintype "passive"))
      (node (ref "R9") (pin "2") (pinfunction "2_2") (pintype "passive"))
      (node (ref "T1") (pin "5") (pinfunction "G_5") (pintype "passive"))
    )
    (net (code "55") (name "Net-(T1B-S)") (class "Default")
      (node (ref "CENTER") (pin "P$1") (pinfunction "P$1_P$1") (pintype "bidirectional"))
      (node (ref "CENTER") (pin "P$4") (pinfunction "P$1_P$4") (pintype "bidirectional"))
      (node (ref "D7") (pin "1") (pinfunction "1_1") (pintype "bidirectional"))
      (node (ref "T1") (pin "4") (pinfunction "S_4") (pintype "passive"))
    )
    (net (code "56") (name "Net-(T2B-D)") (class "Default")
      (node (ref "R21") (pin "1") (pinfunction "1_1") (pintype "passive"))
      (node (ref "T2") (pin "3") (pinfunction "D_3") (pintype "passive"))
    )
    (net (code "57") (name "Net-(T2B-G)") (class "Default")
      (node (ref "R20") (pin "2") (pinfunction "2_2") (pintype "passive"))
      (node (ref "R32") (pin "2") (pinfunction "2_2") (pintype "passive"))
      (node (ref "T2") (pin "5") (pinfunction "G_5") (pintype "passive"))
    )
    (net (code "58") (name "Net-(T3A-D)") (class "Default")
      (node (ref "R13") (pin "1") (pinfunction "1_1") (pintype "passive"))
      (node (ref "T3") (pin "6") (pinfunction "D_6") (pintype "passive"))
    )
    (net (code "59") (name "Net-(T3A-G)") (class "Default")
      (node (ref "R14") (pin "2") (pinfunction "2_2") (pintype "passive"))
      (node (ref "R15") (pin "2") (pinfunction "2_2") (pintype "passive"))
      (node (ref "T3") (pin "2") (pinfunction "G_2") (pintype "passive"))
    )
    (net (code "60") (name "Net-(U$6--)") (class "Default")
      (node (ref "D1") (pin "2") (pinfunction "2_2") (pintype "bidirectional"))
      (node (ref "D6") (pin "2") (pinfunction "2_2") (pintype "bidirectional"))
      (node (ref "R21") (pin "2") (pinfunction "2_2") (pintype "passive"))
      (node (ref "U$6") (pin "P$2") (pinfunction "-_P$2") (pintype "passive"))
      (node (ref "U$8") (pin "P$3") (pinfunction "-_P$3") (pintype "passive"))
    )
    (net (code "61") (name "Net-(USB-D+)") (class "Default")
      (node (ref "C2") (pin "2") (pinfunction "2_2") (pintype "passive"))
      (node (ref "R4") (pin "1") (pinfunction "1_1") (pintype "passive"))
      (node (ref "USB") (pin "3") (pinfunction "D+_3") (pintype "passive"))
    )
    (net (code "62") (name "Net-(USB-D-)") (class "Default")
      (node (ref "C3") (pin "2") (pinfunction "2_2") (pintype "passive"))
      (node (ref "R3") (pin "1") (pinfunction "1_1") (pintype "passive"))
      (node (ref "USB") (pin "2") (pinfunction "D-_2") (pintype "passive"))
    )
    (net (code "63") (name "RX0") (class "Default")
      (node (ref "FT231X") (pin "P$17") (pinfunction "TXD_P$17") (pintype "bidirectional"))
      (node (ref "IC3") (pin "40") (pinfunction "U0RXD_40") (pintype "bidirectional"))
      (node (ref "PROG") (pin "4") (pinfunction "4_4") (pintype "passive"))
    )
    (net (code "64") (name "SCK") (class "Default")
      (node (ref "IC3") (pin "16") (pinfunction "IO27_16") (pintype "bidirectional"))
      (node (ref "U$11") (pin "P$4") (pinfunction "SCL_P$4") (pintype "bidirectional"))
    )
    (net (code "65") (name "SENSOR_VN") (class "Default")
      (node (ref "C30") (pin "1") (pinfunction "1_1") (pintype "passive"))
      (node (ref "IC3") (pin "8") (pinfunction "SENSOR_VN_8") (pintype "bidirectional"))
      (node (ref "LS1") (pin "2") (pinfunction "2_2") (pintype "passive"))
      (node (ref "R28") (pin "2") (pinfunction "2_2") (pintype "passive"))
    )
    (net (code "66") (name "TFTCS") (class "Default")
      (node (ref "IC3") (pin "13") (pinfunction "IO33_13") (pintype "bidirectional"))
      (node (ref "U$11") (pin "P$7") (pinfunction "CS_P$7") (pintype "bidirectional"))
    )
    (net (code "67") (name "TX0") (class "Default")
      (node (ref "FT231X") (pin "P$1") (pinfunction "RXD_P$1") (pintype "bidirectional"))
      (node (ref "PROG") (pin "5") (pinfunction "5_5") (pintype "passive"))
      (node (ref "R16") (pin "2") (pinfunction "2_2") (pintype "passive"))
    )
    (net (code "68") (name "VDD_SDIO") (class "Default")
      (node (ref "IC3") (pin "26") (pinfunction "VDD_SDIO_NC_26") (pintype "bidirectional"))
    )
    (net (code "69") (name "unconnected-(FT231X-CBUS0-PadP$15)") (class "Default")
      (node (ref "FT231X") (pin "P$15") (pinfunction "CBUS0_P$15") (pintype "bidirectional"))
    )
    (net (code "70") (name "unconnected-(FT231X-CBUS1-PadP$14)") (class "Default")
      (node (ref "FT231X") (pin "P$14") (pinfunction "CBUS1_P$14") (pintype "bidirectional"))
    )
    (net (code "71") (name "unconnected-(FT231X-CBUS2-PadP$7)") (class "Default")
      (node (ref "FT231X") (pin "P$7") (pinfunction "CBUS2_P$7") (pintype "bidirectional"))
    )
    (net (code "72") (name "unconnected-(FT231X-CBUS3-PadP$16)") (class "Default")
      (node (ref "FT231X") (pin "P$16") (pinfunction "CBUS3_P$16") (pintype "bidirectional"))
    )
    (net (code "73") (name "unconnected-(FT231X-~{CTS}-PadP$6)") (class "Default")
      (node (ref "FT231X") (pin "P$6") (pinfunction "~{CTS}_P$6") (pintype "bidirectional"))
    )
    (net (code "74") (name "unconnected-(FT231X-~{DCD}-PadP$5)") (class "Default")
      (node (ref "FT231X") (pin "P$5") (pinfunction "~{DCD}_P$5") (pintype "bidirectional"))
    )
    (net (code "75") (name "unconnected-(FT231X-~{DSR}-PadP$4)") (class "Default")
      (node (ref "FT231X") (pin "P$4") (pinfunction "~{DSR}_P$4") (pintype "bidirectional"))
    )
    (net (code "76") (name "unconnected-(FT231X-~{RI}-PadP$2)") (class "Default")
      (node (ref "FT231X") (pin "P$2") (pinfunction "~{RI}_P$2") (pintype "bidirectional"))
    )
    (net (code "77") (name "unconnected-(IC3A-CAP1_NC-Pad48)") (class "Default")
      (node (ref "IC3") (pin "48") (pinfunction "CAP1_NC_48") (pintype "bidirectional"))
    )
    (net (code "78") (name "unconnected-(IC3A-CAP2_NC-Pad47)") (class "Default")
      (node (ref "IC3") (pin "47") (pinfunction "CAP2_NC_47") (pintype "bidirectional"))
    )
    (net (code "79") (name "unconnected-(IC3A-IO5-Pad34)") (class "Default")
      (node (ref "IC3") (pin "34") (pinfunction "IO5_34") (pintype "bidirectional"))
    )
    (net (code "80") (name "unconnected-(IC3A-IO34-Pad10)") (class "Default")
      (node (ref "IC3") (pin "10") (pinfunction "IO34_10") (pintype "bidirectional"))
    )
    (net (code "81") (name "unconnected-(IC3A-SENSOR_CAPP-Pad6)") (class "Default")
      (node (ref "IC3") (pin "6") (pinfunction "SENSOR_CAPP_6") (pintype "bidirectional"))
    )
    (net (code "82") (name "unconnected-(IC3A-SENSOR_VP-Pad5)") (class "Default")
      (node (ref "IC3") (pin "5") (pinfunction "SENSOR_VP_5") (pintype "bidirectional"))
    )
    (net (code "83") (name "unconnected-(IC3A-XTAL_N_NC-Pad44)") (class "Default")
      (node (ref "IC3") (pin "44") (pinfunction "XTAL_N_NC_44") (pintype "bidirectional"))
    )
    (net (code "84") (name "unconnected-(IC3A-XTAL_P_NC-Pad45)") (class "Default")
      (node (ref "IC3") (pin "45") (pinfunction "XTAL_P_NC_45") (pintype "bidirectional"))
    )
    (net (code "85") (name "unconnected-(M365-Pad1)") (class "Default")
      (node (ref "M365") (pin "1") (pinfunction "1_1") (pintype "passive"))
    )
    (net (code "86") (name "unconnected-(USB-ID-Pad4)") (class "Default")
      (node (ref "USB") (pin "4") (pinfunction "ID_4") (pintype "passive"))
    )
  )
)
